# power-synth.net
KiCad netlist of a schematic drawn in Altium Designer
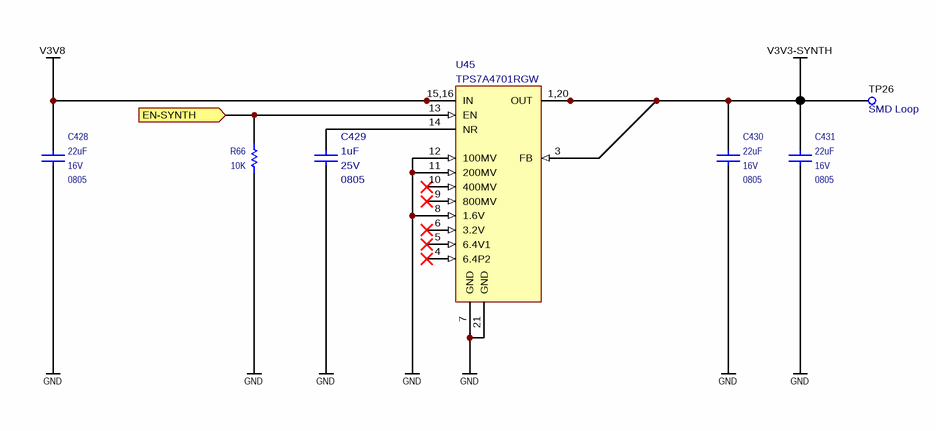
[diagram p0: power-synth.SchDoc]

(export (version "E")
  (design (tool "Eeschema 10.0.6"))
  (components
    (comp (ref "C428")
      (value "22uF")
      (footprint "generic:CAPC200X125X145L45N")
      (description "Ceramic Capacitor 22uF ±10% 16V X5R 0805")
      (fields
        (field (name "MANUFACTURER") "Samsung")
        (field (name "VOLTAGE") "16V")
        (field (name "PACKAGE") "0805")
        (field (name "TOLERANCE") "±10%")
      )
      (libsource (lib "generic") (part "CAP 0603"))
    )
    (comp (ref "C429")
      (value "1uF")
      (footprint "CAPC200X125X145L45N")
      (description "Ceramic Capacitor 1uF ±10% 25V X7R 0805")
      (fields
        (field (name "MANUFACTURER") "Taiyo Yuden")
        (field (name "TOLERANCE") "±10%")
        (field (name "PACKAGE") "0805")
        (field (name "VOLTAGE") "25V")
      )
      (libsource (lib "capacitors") (part "CAP"))
    )
    (comp (ref "C430")
      (value "22uF")
      (footprint "generic:CAPC200X125X145L45N")
      (description "Ceramic Capacitor 22uF ±10% 16V X5R 0805")
      (fields
        (field (name "MANUFACTURER") "Samsung")
        (field (name "VOLTAGE") "16V")
        (field (name "PACKAGE") "0805")
        (field (name "TOLERANCE") "±10%")
      )
      (libsource (lib "generic") (part "CAP 0603"))
    )
    (comp (ref "C431")
      (value "22uF")
      (footprint "generic:CAPC200X125X145L45N")
      (description "Ceramic Capacitor 22uF ±10% 16V X5R 0805")
      (fields
        (field (name "MANUFACTURER") "Samsung")
        (field (name "VOLTAGE") "16V")
        (field (name "PACKAGE") "0805")
        (field (name "TOLERANCE") "±10%")
      )
      (libsource (lib "generic") (part "CAP 0603"))
    )
    (comp (ref "R66")
      (value "10K")
      (footprint "RESC1005X40N")
      (description "Thick Film Resistor 10k ±1% 0.1W 50V 0402")
      (fields (field (name "MANUFACTURER") "Panasonic") (field (name "TOLERANCE") "±1%"))
      (libsource (lib "Graviton") (part "RES 0402"))
    )
    (comp (ref "TP26")
      (value "5015")
      (footprint "keystone:5015")
      (description "Test Point SMD")
      (fields (field (name "MANUFACTURER") "Keystone") (field (name "NOTES") "SMD Loop"))
      (libsource (lib "generic") (part "TEST_POINT_SMD_50"))
    )
    (comp (ref "U45")
      (value "TPS7A4701RGW")
      (footprint "QFN65P500X500X100-21N")
      (description "Low-Dropout Linear Regulator 20-VQFN")
      (fields (field (name "MANUFACTURER") "Texas Instruments"))
      (libsource (lib "ti") (part "TPS7A4701RGW_1"))
    )
  )
  (nets
    (net (code "1") (name "/EN-SYNTH") (class "Default")
      (node (ref "R66") (pin "1") (pinfunction "1_1") (pintype "passive"))
      (node (ref "U45") (pin "13") (pinfunction "EN_13") (pintype "input"))
    )
    (net (code "2") (name "GND") (class "Default")
      (node (ref "C428") (pin "1") (pinfunction "1_1") (pintype "passive"))
      (node (ref "C429") (pin "2") (pinfunction "2_2") (pintype "passive"))
      (node (ref "C430") (pin "1") (pinfunction "1_1") (pintype "passive"))
      (node (ref "C431") (pin "1") (pinfunction "1_1") (pintype "passive"))
      (node (ref "R66") (pin "2") (pinfunction "2_2") (pintype "passive"))
      (node (ref "U45") (pin "11") (pinfunction "200MV_11") (pintype "input"))
      (node (ref "U45") (pin "12") (pinfunction "100MV_12") (pintype "input"))
      (node (ref "U45") (pin "21") (pinfunction "GND_21") (pintype "power_in"))
      (node (ref "U45") (pin "7") (pinfunction "GND_7") (pintype "power_in"))
      (node (ref "U45") (pin "8") (pinfunction "1.6V_8") (pintype "input"))
    )
    (net (code "3") (name "Net-(U45-NR)") (class "Default")
      (node (ref "C429") (pin "1") (pinfunction "1_1") (pintype "passive"))
      (node (ref "U45") (pin "14") (pinfunction "NR_14") (pintype "passive"))
    )
    (net (code "4") (name "V3V3-SYNTH") (class "Default")
      (node (ref "C430") (pin "2") (pinfunction "2_2") (pintype "passive"))
      (node (ref "C431") (pin "2") (pinfunction "2_2") (pintype "passive"))
      (node (ref "TP26") (pin "1") (pinfunction "1_1") (pintype "passive"))
      (node (ref "U45") (pin "1") (pinfunction "OUT_1") (pintype "passive"))
      (node (ref "U45") (pin "20") (pinfunction "OUT_20") (pintype "passive"))
      (node (ref "U45") (pin "3") (pinfunction "FB_3") (pintype "input"))
    )
    (net (code "5") (name "V3V8") (class "Default")
      (node (ref "C428") (pin "2") (pinfunction "2_2") (pintype "passive"))
      (node (ref "U45") (pin "15") (pinfunction "IN_15") (pintype "passive"))
      (node (ref "U45") (pin "16") (pinfunction "IN_16") (pintype "passive"))
    )
    (net (code "6") (name "unconnected-(U45-3.2V-Pad6)") (class "Default")
      (node (ref "U45") (pin "6") (pinfunction "3.2V_6") (pintype "input+no_connect"))
    )
    (net (code "7") (name "unconnected-(U45-6.4P2-Pad4)") (class "Default")
      (node (ref "U45") (pin "4") (pinfunction "6.4P2_4") (pintype "input+no_connect"))
    )
    (net (code "8") (name "unconnected-(U45-6.4V1-Pad5)") (class "Default")
      (node (ref "U45") (pin "5") (pinfunction "6.4V1_5") (pintype "input+no_connect"))
    )
    (net (code "9") (name "unconnected-(U45-400MV-Pad10)") (class "Default")
      (node (ref "U45") (pin "10") (pinfunction "400MV_10") (pintype "input+no_connect"))
    )
    (net (code "10") (name "unconnected-(U45-800MV-Pad9)") (class "Default")
      (node (ref "U45") (pin "9") (pinfunction "800MV_9") (pintype "input+no_connect"))
    )
  )
)
